# Bridge_Pair_1.net
KiCad netlist of a schematic drawn in Altium Designer
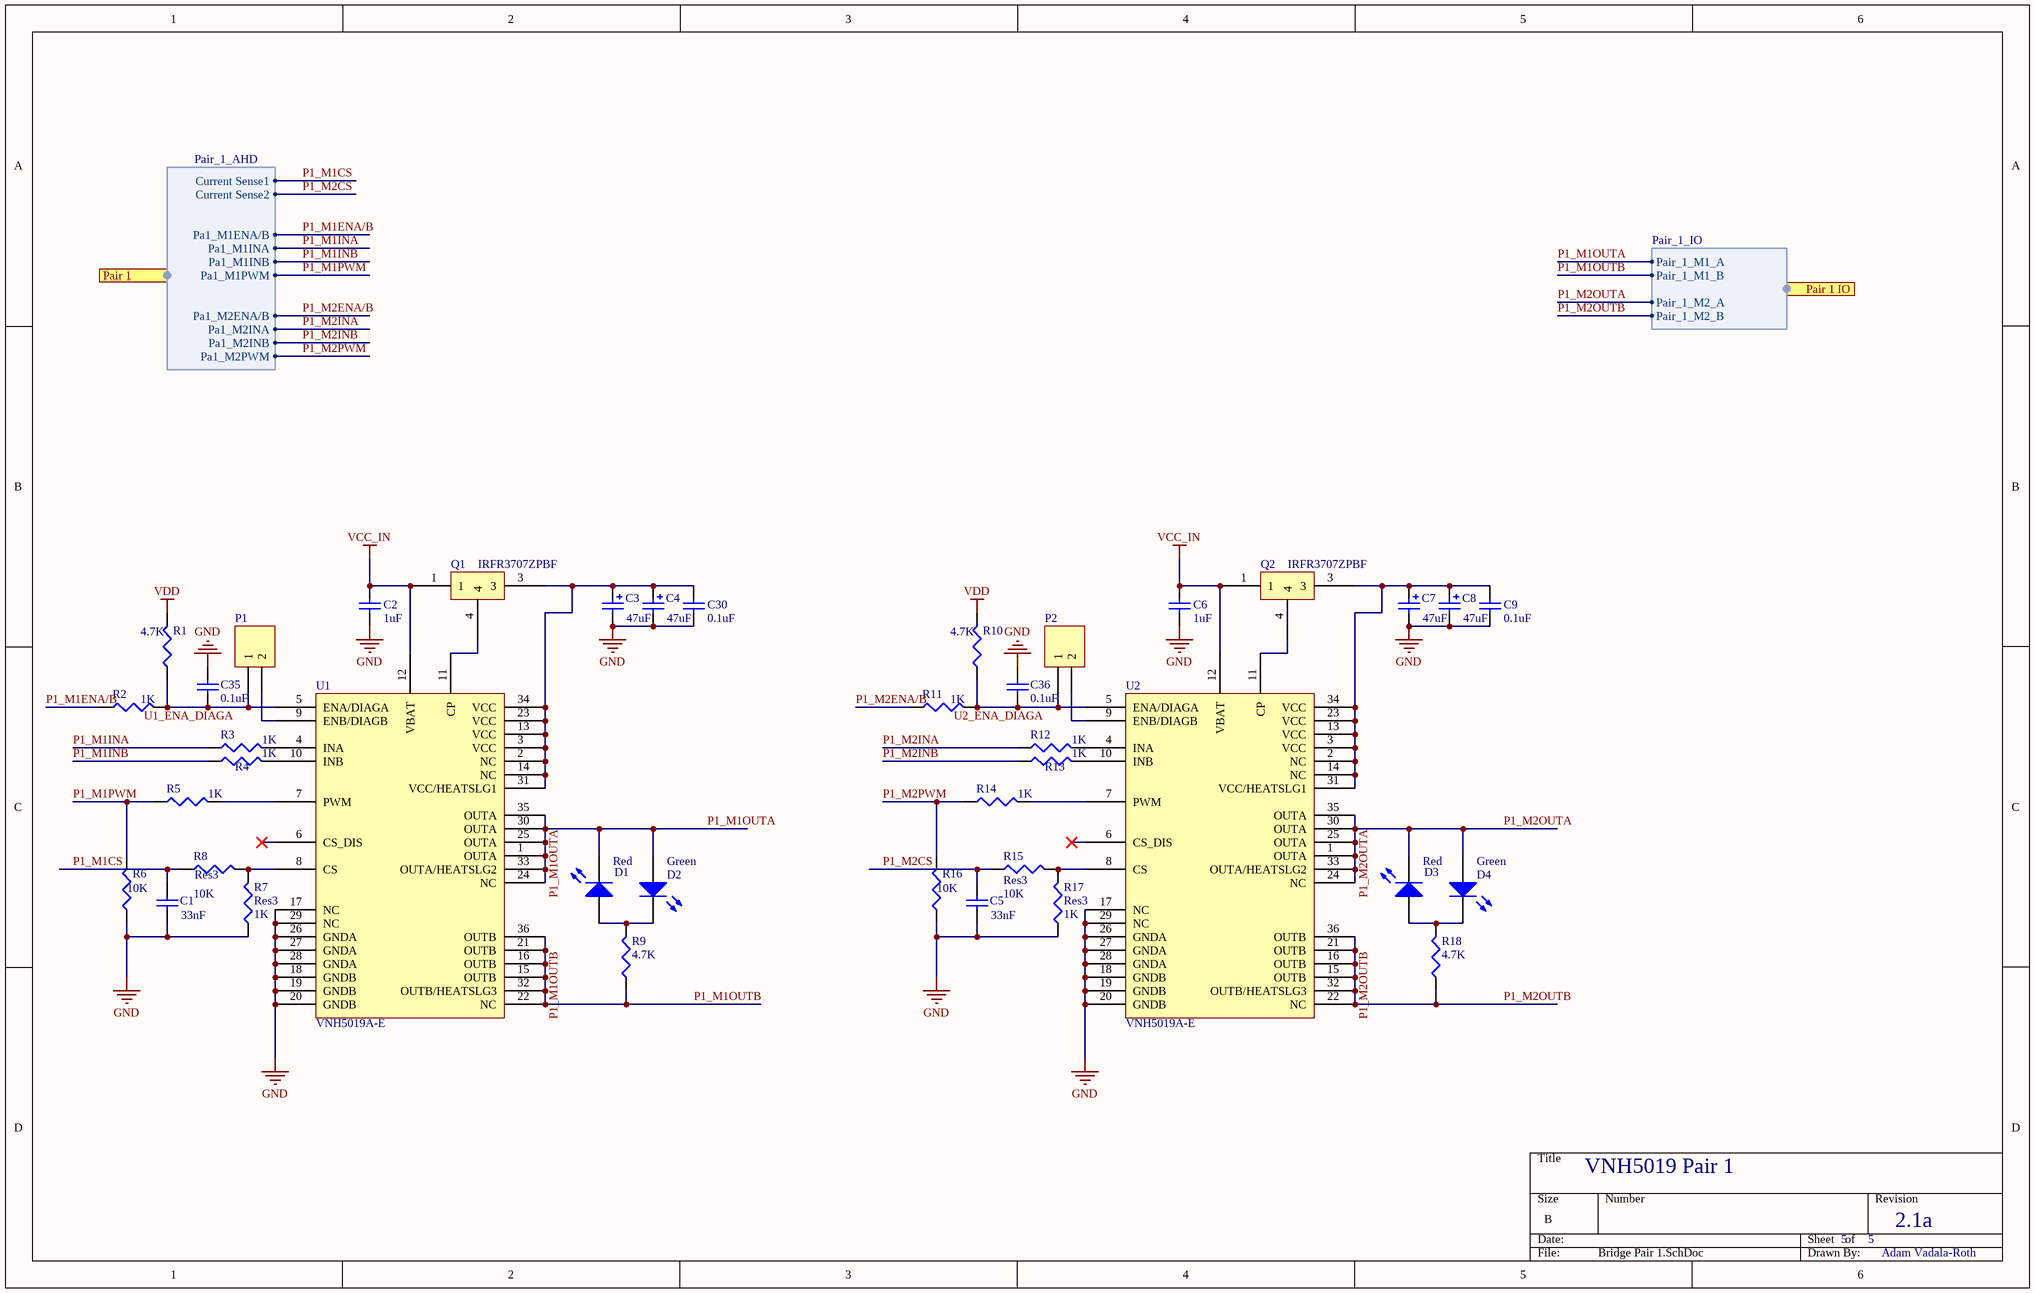
[diagram p0: Bridge Pair 1.SchDoc]

(export (version "E")
  (design (tool "Eeschema 10.0.6"))
  (components
    (comp (ref "C1")
      (value "33nF")
      (footprint "1608[0603]")
      (description "Capacitor (Semiconductor SIM Model)")
      (fields (field (name "Comment") "Cap Semi") (field (name "PUBLISHER") "Altium Limited"))
      (libsource (lib "Miscellaneous Devices") (part "Cap Semi"))
    )
    (comp (ref "C2")
      (value "1uF")
      (footprint "1608[0603]")
      (description "Capacitor (Semiconductor SIM Model)")
      (fields (field (name "Comment") "Cap Semi") (field (name "PUBLISHER") "Altium Limited"))
      (libsource (lib "Miscellaneous Devices") (part "Cap Semi"))
    )
    (comp (ref "C3")
      (value "47uF")
      (footprint "CAPPR2-5x6.8")
      (description "Polarized Capacitor (Axial)")
      (fields (field (name "Comment") "Cap Pol2") (field (name "PUBLISHER") "Altium Limited"))
      (libsource (lib "Miscellaneous Devices") (part "Cap Pol2"))
    )
    (comp (ref "C4")
      (value "47uF")
      (footprint "CAPPR2-5x6.8")
      (description "Polarized Capacitor (Axial)")
      (fields (field (name "Comment") "Cap Pol2") (field (name "PUBLISHER") "Altium Limited"))
      (libsource (lib "Miscellaneous Devices") (part "Cap Pol2"))
    )
    (comp (ref "C5")
      (value "33nF")
      (footprint "1608[0603]")
      (description "Capacitor (Semiconductor SIM Model)")
      (fields (field (name "Comment") "Cap Semi") (field (name "PUBLISHER") "Altium Limited"))
      (libsource (lib "Miscellaneous Devices") (part "Cap Semi"))
    )
    (comp (ref "C6")
      (value "1uF")
      (footprint "1608[0603]")
      (description "Capacitor (Semiconductor SIM Model)")
      (fields (field (name "Comment") "Cap Semi") (field (name "PUBLISHER") "Altium Limited"))
      (libsource (lib "Miscellaneous Devices") (part "Cap Semi"))
    )
    (comp (ref "C7")
      (value "47uF")
      (footprint "CAPPR2-5x6.8")
      (description "Polarized Capacitor (Axial)")
      (fields (field (name "Comment") "Cap Pol2") (field (name "PUBLISHER") "Altium Limited"))
      (libsource (lib "Miscellaneous Devices") (part "Cap Pol2"))
    )
    (comp (ref "C8")
      (value "47uF")
      (footprint "CAPPR2-5x6.8")
      (description "Polarized Capacitor (Axial)")
      (fields (field (name "Comment") "Cap Pol2") (field (name "PUBLISHER") "Altium Limited"))
      (libsource (lib "Miscellaneous Devices") (part "Cap Pol2"))
    )
    (comp (ref "C9")
      (value "0.1uF")
      (footprint "C1206")
      (description "Capacitor (Semiconductor SIM Model)")
      (fields (field (name "Comment") "Cap Semi") (field (name "PUBLISHER") "Altium Limited"))
      (libsource (lib "Miscellaneous Devices") (part "Cap Semi"))
    )
    (comp (ref "C30")
      (value "0.1uF")
      (footprint "C1206")
      (description "Capacitor (Semiconductor SIM Model)")
      (fields (field (name "Comment") "Cap Semi") (field (name "PUBLISHER") "Altium Limited"))
      (libsource (lib "Miscellaneous Devices") (part "Cap Semi"))
    )
    (comp (ref "C35")
      (value "0.1uF")
      (footprint "1608[0603]")
      (description "Capacitor (Semiconductor SIM Model)")
      (fields (field (name "Comment") "Cap Semi") (field (name "PUBLISHER") "Altium Limited"))
      (libsource (lib "Miscellaneous Devices") (part "Cap Semi"))
    )
    (comp (ref "C36")
      (value "0.1uF")
      (footprint "1608[0603]")
      (description "Capacitor (Semiconductor SIM Model)")
      (fields (field (name "Comment") "Cap Semi") (field (name "PUBLISHER") "Altium Limited"))
      (libsource (lib "Miscellaneous Devices") (part "Cap Semi"))
    )
    (comp (ref "D1")
      (value "LED2")
      (footprint "3.2X1.6X1.1")
      (description "Typical RED, GREEN, YELLOW, AMBER GaAs LED")
      (fields (field (name "PUBLISHER") "Altium Limited"))
      (libsource (lib "Miscellaneous Devices") (part "LED2"))
    )
    (comp (ref "D2")
      (value "LED2")
      (footprint "3.2X1.6X1.1")
      (description "Typical RED, GREEN, YELLOW, AMBER GaAs LED")
      (fields (field (name "PUBLISHER") "Altium Limited"))
      (libsource (lib "Miscellaneous Devices") (part "LED2"))
    )
    (comp (ref "D3")
      (value "LED2")
      (footprint "3.2X1.6X1.1")
      (description "Typical RED, GREEN, YELLOW, AMBER GaAs LED")
      (fields (field (name "PUBLISHER") "Altium Limited"))
      (libsource (lib "Miscellaneous Devices") (part "LED2"))
    )
    (comp (ref "D4")
      (value "LED2")
      (footprint "3.2X1.6X1.1")
      (description "Typical RED, GREEN, YELLOW, AMBER GaAs LED")
      (fields (field (name "PUBLISHER") "Altium Limited"))
      (libsource (lib "Miscellaneous Devices") (part "LED2"))
    )
    (comp (ref "P1")
      (value "Header 2")
      (footprint "HDR1X2")
      (description "Header, 2-Pin")
      (fields (field (name "PUBLISHER") "Altium Limited"))
      (libsource (lib "Miscellaneous Connectors") (part "Header 2"))
    )
    (comp (ref "P2")
      (value "Header 2")
      (footprint "HDR1X2")
      (description "Header, 2-Pin")
      (fields (field (name "PUBLISHER") "Altium Limited"))
      (libsource (lib "Miscellaneous Connectors") (part "Header 2"))
    )
    (comp (ref "Q1")
      (value "IRFR3707ZPBF")
      (footprint "IRFR3707ZPBF")
      (description "Power FET")
      (libsource (lib "Thruster Shield Part Library") (part "IRFR3707ZPBF"))
    )
    (comp (ref "Q2")
      (value "IRFR3707ZPBF")
      (footprint "IRFR3707ZPBF")
      (description "Power FET")
      (libsource (lib "Thruster Shield Part Library") (part "IRFR3707ZPBF"))
    )
    (comp (ref "R1")
      (value "4.7K")
      (footprint "RESC1608L")
      (description "Resistor")
      (fields (field (name "Comment") "Res3") (field (name "PUBLISHER") "Altium Limited"))
      (libsource (lib "Miscellaneous Devices") (part "Res3"))
    )
    (comp (ref "R2")
      (value "1K")
      (footprint "RESC1608L")
      (description "Resistor")
      (fields (field (name "Comment") "Res3") (field (name "PUBLISHER") "Altium Limited"))
      (libsource (lib "Miscellaneous Devices") (part "Res3"))
    )
    (comp (ref "R3")
      (value "1K")
      (footprint "RESC1608L")
      (description "Resistor")
      (fields (field (name "Comment") "Res3") (field (name "PUBLISHER") "Altium Limited"))
      (libsource (lib "Miscellaneous Devices") (part "Res3"))
    )
    (comp (ref "R4")
      (value "1K")
      (footprint "RESC1608L")
      (description "Resistor")
      (fields (field (name "Comment") "Res3") (field (name "PUBLISHER") "Altium Limited"))
      (libsource (lib "Miscellaneous Devices") (part "Res3"))
    )
    (comp (ref "R5")
      (value "1K")
      (footprint "RESC1608L")
      (description "Resistor")
      (fields (field (name "Comment") "Res3") (field (name "PUBLISHER") "Altium Limited"))
      (libsource (lib "Miscellaneous Devices") (part "Res3"))
    )
    (comp (ref "R6")
      (value "10K")
      (footprint "RESC1608L")
      (description "Resistor")
      (fields (field (name "Comment") "Res3") (field (name "PUBLISHER") "Altium Limited"))
      (libsource (lib "Miscellaneous Devices") (part "Res3"))
    )
    (comp (ref "R7")
      (value "Res3")
      (footprint "RESC1608L")
      (description "Resistor")
      (fields (field (name "ALTIUM_VALUE") "1K") (field (name "PUBLISHER") "Altium Limited"))
      (libsource (lib "Miscellaneous Devices") (part "Res3"))
    )
    (comp (ref "R8")
      (value "Res3")
      (footprint "RESC1608L")
      (description "Resistor")
      (fields (field (name "ALTIUM_VALUE") "10K") (field (name "PUBLISHER") "Altium Limited"))
      (libsource (lib "Miscellaneous Devices") (part "Res3"))
    )
    (comp (ref "R9")
      (value "4.7K")
      (footprint "0805 SMD Resistor")
      (description "Resistor")
      (fields (field (name "Comment") "Res3") (field (name "PUBLISHER") "Altium Limited"))
      (libsource (lib "Miscellaneous Devices") (part "Res3"))
    )
    (comp (ref "R10")
      (value "4.7K")
      (footprint "RESC1608L")
      (description "Resistor")
      (fields (field (name "Comment") "Res3") (field (name "PUBLISHER") "Altium Limited"))
      (libsource (lib "Miscellaneous Devices") (part "Res3"))
    )
    (comp (ref "R11")
      (value "1K")
      (footprint "RESC1608L")
      (description "Resistor")
      (fields (field (name "Comment") "Res3") (field (name "PUBLISHER") "Altium Limited"))
      (libsource (lib "Miscellaneous Devices") (part "Res3"))
    )
    (comp (ref "R12")
      (value "1K")
      (footprint "RESC1608L")
      (description "Resistor")
      (fields (field (name "Comment") "Res3") (field (name "PUBLISHER") "Altium Limited"))
      (libsource (lib "Miscellaneous Devices") (part "Res3"))
    )
    (comp (ref "R13")
      (value "1K")
      (footprint "RESC1608L")
      (description "Resistor")
      (fields (field (name "Comment") "Res3") (field (name "PUBLISHER") "Altium Limited"))
      (libsource (lib "Miscellaneous Devices") (part "Res3"))
    )
    (comp (ref "R14")
      (value "1K")
      (footprint "RESC1608L")
      (description "Resistor")
      (fields (field (name "Comment") "Res3") (field (name "PUBLISHER") "Altium Limited"))
      (libsource (lib "Miscellaneous Devices") (part "Res3"))
    )
    (comp (ref "R15")
      (value "Res3")
      (footprint "RESC1608L")
      (description "Resistor")
      (fields (field (name "ALTIUM_VALUE") "10K") (field (name "PUBLISHER") "Altium Limited"))
      (libsource (lib "Miscellaneous Devices") (part "Res3"))
    )
    (comp (ref "R16")
      (value "10K")
      (footprint "RESC1608L")
      (description "Resistor")
      (fields (field (name "Comment") "Res3") (field (name "PUBLISHER") "Altium Limited"))
      (libsource (lib "Miscellaneous Devices") (part "Res3"))
    )
    (comp (ref "R17")
      (value "Res3")
      (footprint "RESC1608L")
      (description "Resistor")
      (fields (field (name "ALTIUM_VALUE") "1K") (field (name "PUBLISHER") "Altium Limited"))
      (libsource (lib "Miscellaneous Devices") (part "Res3"))
    )
    (comp (ref "R18")
      (value "4.7K")
      (footprint "0805 SMD Resistor")
      (description "Resistor")
      (fields (field (name "Comment") "Res3") (field (name "PUBLISHER") "Altium Limited"))
      (libsource (lib "Miscellaneous Devices") (part "Res3"))
    )
    (comp (ref "U1")
      (value "VNH5019A-E")
      (footprint "VNH5019A-E")
      (description "VNH5019A-E H-Bridge")
      (libsource (lib "Ballast and Depth Controller Library") (part "VNH5019A-E"))
    )
    (comp (ref "U2")
      (value "VNH5019A-E")
      (footprint "VNH5019A-E")
      (description "VNH5019A-E H-Bridge")
      (libsource (lib "Ballast and Depth Controller Library") (part "VNH5019A-E"))
    )
  )
  (nets
    (net (code "3") (name "/P1_M1CS") (class "Default")
      (node (ref "C1") (pin "2") (pinfunction "2_2") (pintype "passive"))
      (node (ref "R8") (pin "1") (pinfunction "1_1") (pintype "passive"))
    )
    (net (code "4") (name "/P1_M1ENA{slash}B") (class "Default")
      (node (ref "R2") (pin "1") (pinfunction "1_1") (pintype "passive"))
    )
    (net (code "5") (name "/P1_M1INA") (class "Default")
      (node (ref "R3") (pin "1") (pinfunction "1_1") (pintype "passive"))
    )
    (net (code "6") (name "/P1_M1INB") (class "Default")
      (node (ref "R4") (pin "1") (pinfunction "1_1") (pintype "passive"))
    )
    (net (code "7") (name "/P1_M1OUTA") (class "Default")
      (node (ref "D1") (pin "2") (pinfunction "K_2") (pintype "passive"))
      (node (ref "D2") (pin "1") (pinfunction "A_1") (pintype "passive"))
      (node (ref "U1") (pin "1") (pinfunction "OUTA_1") (pintype "passive"))
      (node (ref "U1") (pin "24") (pinfunction "NC_24") (pintype "passive"))
      (node (ref "U1") (pin "25") (pinfunction "OUTA_25") (pintype "passive"))
      (node (ref "U1") (pin "30") (pinfunction "OUTA_30") (pintype "passive"))
      (node (ref "U1") (pin "33") (pinfunction "OUTA/HEATSLG2_33") (pintype "passive"))
      (node (ref "U1") (pin "35") (pinfunction "OUTA_35") (pintype "passive"))
    )
    (net (code "8") (name "/P1_M1OUTB") (class "Default")
      (node (ref "R9") (pin "1") (pinfunction "1_1") (pintype "passive"))
      (node (ref "U1") (pin "15") (pinfunction "OUTB_15") (pintype "passive"))
      (node (ref "U1") (pin "16") (pinfunction "OUTB_16") (pintype "passive"))
      (node (ref "U1") (pin "21") (pinfunction "OUTB_21") (pintype "passive"))
      (node (ref "U1") (pin "22") (pinfunction "NC_22") (pintype "passive"))
      (node (ref "U1") (pin "32") (pinfunction "OUTB/HEATSLG3_32") (pintype "passive"))
      (node (ref "U1") (pin "36") (pinfunction "OUTB_36") (pintype "passive"))
    )
    (net (code "9") (name "/P1_M1PWM") (class "Default")
      (node (ref "R5") (pin "1") (pinfunction "1_1") (pintype "passive"))
      (node (ref "R6") (pin "2") (pinfunction "2_2") (pintype "passive"))
    )
    (net (code "10") (name "/P1_M2CS") (class "Default")
      (node (ref "C5") (pin "2") (pinfunction "2_2") (pintype "passive"))
      (node (ref "R15") (pin "1") (pinfunction "1_1") (pintype "passive"))
    )
    (net (code "11") (name "/P1_M2ENA{slash}B") (class "Default")
      (node (ref "R11") (pin "1") (pinfunction "1_1") (pintype "passive"))
    )
    (net (code "12") (name "/P1_M2INA") (class "Default")
      (node (ref "R12") (pin "1") (pinfunction "1_1") (pintype "passive"))
    )
    (net (code "13") (name "/P1_M2INB") (class "Default")
      (node (ref "R13") (pin "1") (pinfunction "1_1") (pintype "passive"))
    )
    (net (code "14") (name "/P1_M2OUTA") (class "Default")
      (node (ref "D3") (pin "2") (pinfunction "K_2") (pintype "passive"))
      (node (ref "D4") (pin "1") (pinfunction "A_1") (pintype "passive"))
      (node (ref "U2") (pin "1") (pinfunction "OUTA_1") (pintype "passive"))
      (node (ref "U2") (pin "24") (pinfunction "NC_24") (pintype "passive"))
      (node (ref "U2") (pin "25") (pinfunction "OUTA_25") (pintype "passive"))
      (node (ref "U2") (pin "30") (pinfunction "OUTA_30") (pintype "passive"))
      (node (ref "U2") (pin "33") (pinfunction "OUTA/HEATSLG2_33") (pintype "passive"))
      (node (ref "U2") (pin "35") (pinfunction "OUTA_35") (pintype "passive"))
    )
    (net (code "15") (name "/P1_M2OUTB") (class "Default")
      (node (ref "R18") (pin "1") (pinfunction "1_1") (pintype "passive"))
      (node (ref "U2") (pin "15") (pinfunction "OUTB_15") (pintype "passive"))
      (node (ref "U2") (pin "16") (pinfunction "OUTB_16") (pintype "passive"))
      (node (ref "U2") (pin "21") (pinfunction "OUTB_21") (pintype "passive"))
      (node (ref "U2") (pin "22") (pinfunction "NC_22") (pintype "passive"))
      (node (ref "U2") (pin "32") (pinfunction "OUTB/HEATSLG3_32") (pintype "passive"))
      (node (ref "U2") (pin "36") (pinfunction "OUTB_36") (pintype "passive"))
    )
    (net (code "16") (name "/P1_M2PWM") (class "Default")
      (node (ref "R14") (pin "1") (pinfunction "1_1") (pintype "passive"))
      (node (ref "R16") (pin "2") (pinfunction "2_2") (pintype "passive"))
    )
    (net (code "17") (name "/U1_ENA_DIAGA") (class "Default")
      (node (ref "C35") (pin "2") (pinfunction "2_2") (pintype "passive"))
      (node (ref "P1") (pin "1") (pinfunction "1_1") (pintype "passive"))
      (node (ref "R1") (pin "1") (pinfunction "1_1") (pintype "passive"))
      (node (ref "R2") (pin "2") (pinfunction "2_2") (pintype "passive"))
      (node (ref "U1") (pin "5") (pinfunction "ENA/DIAGA_5") (pintype "passive"))
    )
    (net (code "18") (name "/U2_ENA_DIAGA") (class "Default")
      (node (ref "C36") (pin "2") (pinfunction "2_2") (pintype "passive"))
      (node (ref "P2") (pin "1") (pinfunction "1_1") (pintype "passive"))
      (node (ref "R10") (pin "1") (pinfunction "1_1") (pintype "passive"))
      (node (ref "R11") (pin "2") (pinfunction "2_2") (pintype "passive"))
      (node (ref "U2") (pin "5") (pinfunction "ENA/DIAGA_5") (pintype "passive"))
    )
    (net (code "21") (name "GND") (class "Default")
      (node (ref "C1") (pin "1") (pinfunction "1_1") (pintype "passive"))
      (node (ref "C2") (pin "1") (pinfunction "1_1") (pintype "passive"))
      (node (ref "C3") (pin "2") (pinfunction "2_2") (pintype "passive"))
      (node (ref "C30") (pin "1") (pinfunction "1_1") (pintype "passive"))
      (node (ref "C35") (pin "1") (pinfunction "1_1") (pintype "passive"))
      (node (ref "C36") (pin "1") (pinfunction "1_1") (pintype "passive"))
      (node (ref "C4") (pin "2") (pinfunction "2_2") (pintype "passive"))
      (node (ref "C5") (pin "1") (pinfunction "1_1") (pintype "passive"))
      (node (ref "C6") (pin "1") (pinfunction "1_1") (pintype "passive"))
      (node (ref "C7") (pin "2") (pinfunction "2_2") (pintype "passive"))
      (node (ref "C8") (pin "2") (pinfunction "2_2") (pintype "passive"))
      (node (ref "C9") (pin "1") (pinfunction "1_1") (pintype "passive"))
      (node (ref "R16") (pin "1") (pinfunction "1_1") (pintype "passive"))
      (node (ref "R17") (pin "1") (pinfunction "1_1") (pintype "passive"))
      (node (ref "R6") (pin "1") (pinfunction "1_1") (pintype "passive"))
      (node (ref "R7") (pin "1") (pinfunction "1_1") (pintype "passive"))
      (node (ref "U1") (pin "17") (pinfunction "NC_17") (pintype "passive"))
      (node (ref "U1") (pin "18") (pinfunction "GNDB_18") (pintype "passive"))
      (node (ref "U1") (pin "19") (pinfunction "GNDB_19") (pintype "passive"))
      (node (ref "U1") (pin "20") (pinfunction "GNDB_20") (pintype "passive"))
      (node (ref "U1") (pin "26") (pinfunction "GNDA_26") (pintype "passive"))
      (node (ref "U1") (pin "27") (pinfunction "GNDA_27") (pintype "passive"))
      (node (ref "U1") (pin "28") (pinfunction "GNDA_28") (pintype "passive"))
      (node (ref "U1") (pin "29") (pinfunction "NC_29") (pintype "passive"))
      (node (ref "U2") (pin "17") (pinfunction "NC_17") (pintype "passive"))
      (node (ref "U2") (pin "18") (pinfunction "GNDB_18") (pintype "passive"))
      (node (ref "U2") (pin "19") (pinfunction "GNDB_19") (pintype "passive"))
      (node (ref "U2") (pin "20") (pinfunction "GNDB_20") (pintype "passive"))
      (node (ref "U2") (pin "26") (pinfunction "GNDA_26") (pintype "passive"))
      (node (ref "U2") (pin "27") (pinfunction "GNDA_27") (pintype "passive"))
      (node (ref "U2") (pin "28") (pinfunction "GNDA_28") (pintype "passive"))
      (node (ref "U2") (pin "29") (pinfunction "NC_29") (pintype "passive"))
    )
    (net (code "22") (name "Net-(D1-A)") (class "Default")
      (node (ref "D1") (pin "1") (pinfunction "A_1") (pintype "passive"))
      (node (ref "D2") (pin "2") (pinfunction "K_2") (pintype "passive"))
      (node (ref "R9") (pin "2") (pinfunction "2_2") (pintype "passive"))
    )
    (net (code "23") (name "Net-(D3-A)") (class "Default")
      (node (ref "D3") (pin "1") (pinfunction "A_1") (pintype "passive"))
      (node (ref "D4") (pin "2") (pinfunction "K_2") (pintype "passive"))
      (node (ref "R18") (pin "2") (pinfunction "2_2") (pintype "passive"))
    )
    (net (code "24") (name "Net-(U1-CP)") (class "Default")
      (node (ref "Q1") (pin "4") (pinfunction "4_4") (pintype "passive"))
      (node (ref "U1") (pin "11") (pinfunction "CP_11") (pintype "passive"))
    )
    (net (code "25") (name "Net-(U1-CS)") (class "Default")
      (node (ref "R7") (pin "2") (pinfunction "2_2") (pintype "passive"))
      (node (ref "R8") (pin "2") (pinfunction "2_2") (pintype "passive"))
      (node (ref "U1") (pin "8") (pinfunction "CS_8") (pintype "passive"))
    )
    (net (code "26") (name "Net-(U1-ENB{slash}DIAGB)") (class "Default")
      (node (ref "P1") (pin "2") (pinfunction "2_2") (pintype "passive"))
      (node (ref "U1") (pin "9") (pinfunction "ENB/DIAGB_9") (pintype "passive"))
    )
    (net (code "27") (name "Net-(U1-INA)") (class "Default")
      (node (ref "R3") (pin "2") (pinfunction "2_2") (pintype "passive"))
      (node (ref "U1") (pin "4") (pinfunction "INA_4") (pintype "passive"))
    )
    (net (code "28") (name "Net-(U1-INB)") (class "Default")
      (node (ref "R4") (pin "2") (pinfunction "2_2") (pintype "passive"))
      (node (ref "U1") (pin "10") (pinfunction "INB_10") (pintype "passive"))
    )
    (net (code "29") (name "Net-(U1-PWM)") (class "Default")
      (node (ref "R5") (pin "2") (pinfunction "2_2") (pintype "passive"))
      (node (ref "U1") (pin "7") (pinfunction "PWM_7") (pintype "passive"))
    )
    (net (code "30") (name "Net-(U1-VCC{slash}HEATSLG1)") (class "Default")
      (node (ref "C3") (pin "1") (pinfunction "1_1") (pintype "passive"))
      (node (ref "C30") (pin "2") (pinfunction "2_2") (pintype "passive"))
      (node (ref "C4") (pin "1") (pinfunction "1_1") (pintype "passive"))
      (node (ref "Q1") (pin "3") (pinfunction "3_3") (pintype "passive"))
      (node (ref "U1") (pin "13") (pinfunction "VCC_13") (pintype "passive"))
      (node (ref "U1") (pin "14") (pinfunction "NC_14") (pintype "passive"))
      (node (ref "U1") (pin "2") (pinfunction "NC_2") (pintype "passive"))
      (node (ref "U1") (pin "23") (pinfunction "VCC_23") (pintype "passive"))
      (node (ref "U1") (pin "3") (pinfunction "VCC_3") (pintype "passive"))
      (node (ref "U1") (pin "31") (pinfunction "VCC/HEATSLG1_31") (pintype "passive"))
      (node (ref "U1") (pin "34") (pinfunction "VCC_34") (pintype "passive"))
    )
    (net (code "31") (name "Net-(U2-CP)") (class "Default")
      (node (ref "Q2") (pin "4") (pinfunction "4_4") (pintype "passive"))
      (node (ref "U2") (pin "11") (pinfunction "CP_11") (pintype "passive"))
    )
    (net (code "32") (name "Net-(U2-CS)") (class "Default")
      (node (ref "R15") (pin "2") (pinfunction "2_2") (pintype "passive"))
      (node (ref "R17") (pin "2") (pinfunction "2_2") (pintype "passive"))
      (node (ref "U2") (pin "8") (pinfunction "CS_8") (pintype "passive"))
    )
    (net (code "33") (name "Net-(U2-ENB{slash}DIAGB)") (class "Default")
      (node (ref "P2") (pin "2") (pinfunction "2_2") (pintype "passive"))
      (node (ref "U2") (pin "9") (pinfunction "ENB/DIAGB_9") (pintype "passive"))
    )
    (net (code "34") (name "Net-(U2-INA)") (class "Default")
      (node (ref "R12") (pin "2") (pinfunction "2_2") (pintype "passive"))
      (node (ref "U2") (pin "4") (pinfunction "INA_4") (pintype "passive"))
    )
    (net (code "35") (name "Net-(U2-INB)") (class "Default")
      (node (ref "R13") (pin "2") (pinfunction "2_2") (pintype "passive"))
      (node (ref "U2") (pin "10") (pinfunction "INB_10") (pintype "passive"))
    )
    (net (code "36") (name "Net-(U2-PWM)") (class "Default")
      (node (ref "R14") (pin "2") (pinfunction "2_2") (pintype "passive"))
      (node (ref "U2") (pin "7") (pinfunction "PWM_7") (pintype "passive"))
    )
    (net (code "37") (name "Net-(U2-VCC{slash}HEATSLG1)") (class "Default")
      (node (ref "C7") (pin "1") (pinfunction "1_1") (pintype "passive"))
      (node (ref "C8") (pin "1") (pinfunction "1_1") (pintype "passive"))
      (node (ref "C9") (pin "2") (pinfunction "2_2") (pintype "passive"))
      (node (ref "Q2") (pin "3") (pinfunction "3_3") (pintype "passive"))
      (node (ref "U2") (pin "13") (pinfunction "VCC_13") (pintype "passive"))
      (node (ref "U2") (pin "14") (pinfunction "NC_14") (pintype "passive"))
      (node (ref "U2") (pin "2") (pinfunction "NC_2") (pintype "passive"))
      (node (ref "U2") (pin "23") (pinfunction "VCC_23") (pintype "passive"))
      (node (ref "U2") (pin "3") (pinfunction "VCC_3") (pintype "passive"))
      (node (ref "U2") (pin "31") (pinfunction "VCC/HEATSLG1_31") (pintype "passive"))
      (node (ref "U2") (pin "34") (pinfunction "VCC_34") (pintype "passive"))
    )
    (net (code "38") (name "VCC_IN") (class "Default")
      (node (ref "C2") (pin "2") (pinfunction "2_2") (pintype "passive"))
      (node (ref "C6") (pin "2") (pinfunction "2_2") (pintype "passive"))
      (node (ref "Q1") (pin "1") (pinfunction "1_1") (pintype "passive"))
      (node (ref "Q2") (pin "1") (pinfunction "1_1") (pintype "passive"))
      (node (ref "U1") (pin "12") (pinfunction "VBAT_12") (pintype "passive"))
      (node (ref "U2") (pin "12") (pinfunction "VBAT_12") (pintype "passive"))
    )
    (net (code "39") (name "VDD") (class "Default")
      (node (ref "R1") (pin "2") (pinfunction "2_2") (pintype "passive"))
      (node (ref "R10") (pin "2") (pinfunction "2_2") (pintype "passive"))
    )
    (net (code "40") (name "unconnected-(U1-CS_DIS-Pad6)") (class "Default")
      (node (ref "U1") (pin "6") (pinfunction "CS_DIS_6") (pintype "passive+no_connect"))
    )
    (net (code "41") (name "unconnected-(U2-CS_DIS-Pad6)") (class "Default")
      (node (ref "U2") (pin "6") (pinfunction "CS_DIS_6") (pintype "passive+no_connect"))
    )
  )
)
